# Sensors_CAN.net
KiCad netlist of a schematic drawn in Altium Designer
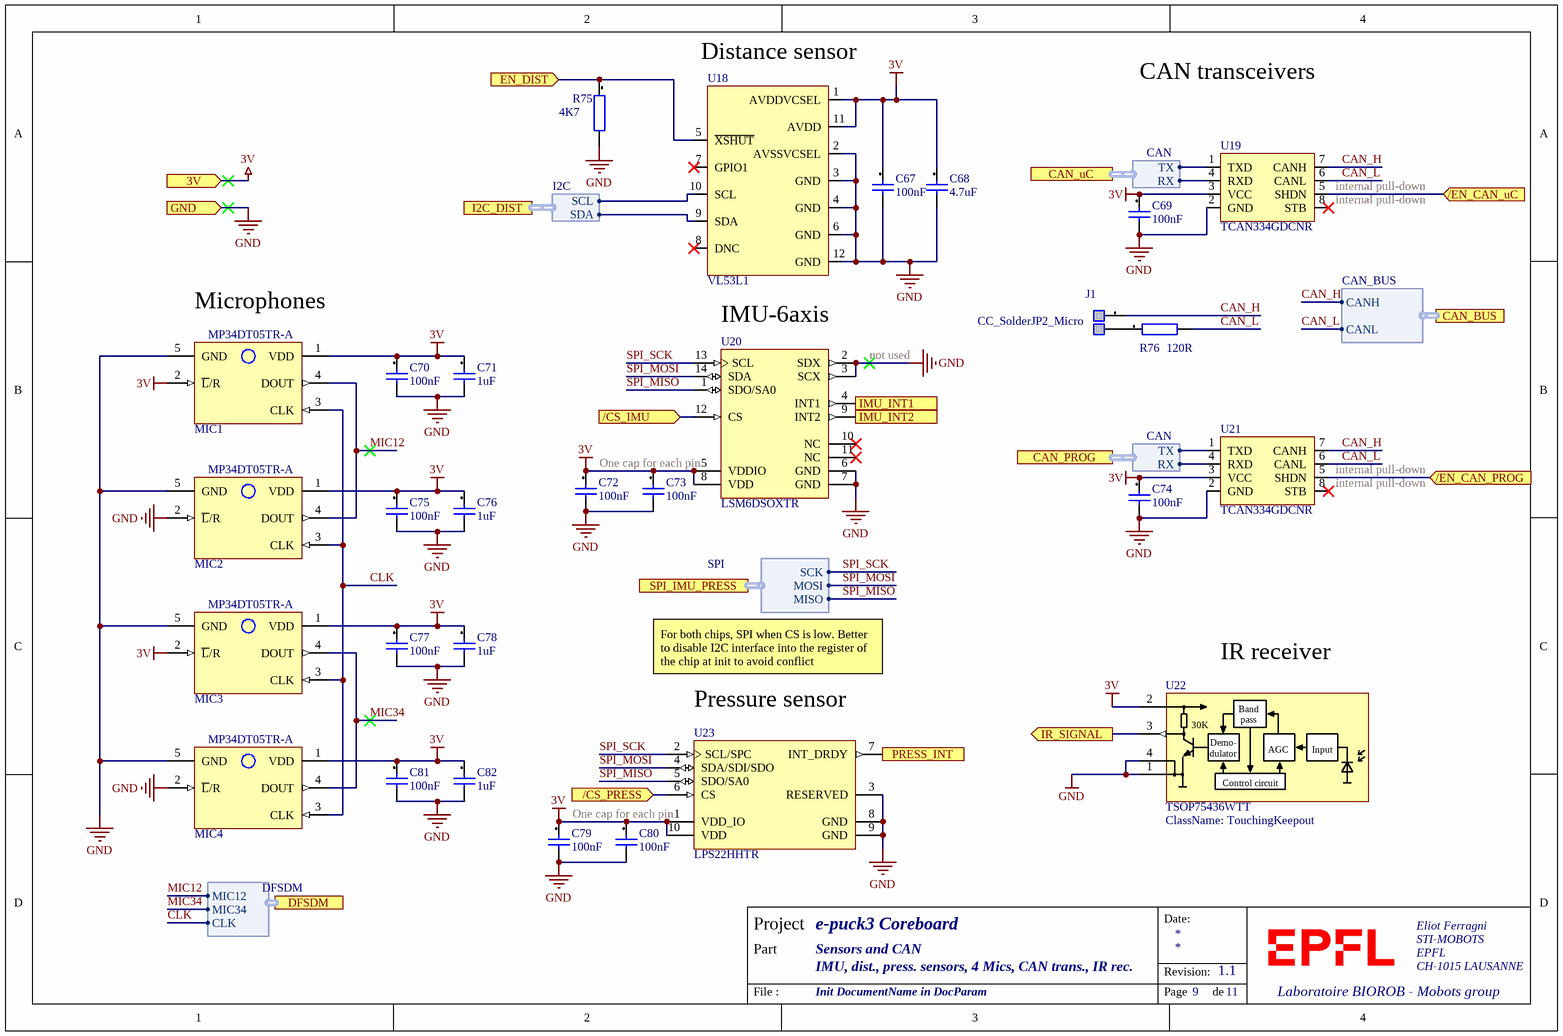
[diagram p0: Sensors + CAN.SchDoc]

(export (version "E")
  (design (tool "Eeschema 10.0.6"))
  (components
    (comp (ref "C67")
      (value "100nF")
      (footprint "CAPC0201(0603)33_L")
      (description "Capacitor 0201")
      (libsource (lib "LSRO1Altium") (part "CAP-NP"))
    )
    (comp (ref "C68")
      (value "4.7uF")
      (footprint "CAPC0201(0603)33_L")
      (description "Capacitor 0201")
      (libsource (lib "LSRO1Altium") (part "CAP-NP"))
    )
    (comp (ref "C69")
      (value "100nF")
      (footprint "CAPC0201(0603)33_L")
      (description "Capacitor 0201")
      (libsource (lib "LSRO1Altium") (part "CAP-NP"))
    )
    (comp (ref "C70")
      (value "100nF")
      (footprint "CAPC0201(0603)33_L")
      (description "Capacitor 0201")
      (libsource (lib "LSRO1Altium") (part "CAP-NP"))
    )
    (comp (ref "C71")
      (value "1uF")
      (footprint "CAPC0201(0603)33_L")
      (description "Capacitor 0201")
      (libsource (lib "LSRO1Altium") (part "CAP-NP"))
    )
    (comp (ref "C72")
      (value "100nF")
      (footprint "CAPC0201(0603)33_L")
      (description "Capacitor 0201")
      (libsource (lib "LSRO1Altium") (part "CAP-NP"))
    )
    (comp (ref "C73")
      (value "100nF")
      (footprint "CAPC0201(0603)33_L")
      (description "Capacitor 0201")
      (libsource (lib "LSRO1Altium") (part "CAP-NP"))
    )
    (comp (ref "C74")
      (value "100nF")
      (footprint "CAPC0201(0603)33_L")
      (description "Capacitor 0201")
      (libsource (lib "LSRO1Altium") (part "CAP-NP"))
    )
    (comp (ref "C75")
      (value "100nF")
      (footprint "CAPC0201(0603)33_L")
      (description "Capacitor 0201")
      (libsource (lib "LSRO1Altium") (part "CAP-NP"))
    )
    (comp (ref "C76")
      (value "1uF")
      (footprint "CAPC0201(0603)33_L")
      (description "Capacitor 0201")
      (libsource (lib "LSRO1Altium") (part "CAP-NP"))
    )
    (comp (ref "C77")
      (value "100nF")
      (footprint "CAPC0201(0603)33_L")
      (description "Capacitor 0201")
      (libsource (lib "LSRO1Altium") (part "CAP-NP"))
    )
    (comp (ref "C78")
      (value "1uF")
      (footprint "CAPC0201(0603)33_L")
      (description "Capacitor 0201")
      (libsource (lib "LSRO1Altium") (part "CAP-NP"))
    )
    (comp (ref "C79")
      (value "100nF")
      (footprint "CAPC0201(0603)33_L")
      (description "Capacitor 0201")
      (libsource (lib "LSRO1Altium") (part "CAP-NP"))
    )
    (comp (ref "C80")
      (value "100nF")
      (footprint "CAPC0201(0603)33_L")
      (description "Capacitor 0201")
      (libsource (lib "LSRO1Altium") (part "CAP-NP"))
    )
    (comp (ref "C81")
      (value "100nF")
      (footprint "CAPC0201(0603)33_L")
      (description "Capacitor 0201")
      (libsource (lib "LSRO1Altium") (part "CAP-NP"))
    )
    (comp (ref "C82")
      (value "1uF")
      (footprint "CAPC0201(0603)33_L")
      (description "Capacitor 0201")
      (libsource (lib "LSRO1Altium") (part "CAP-NP"))
    )
    (comp (ref "J1")
      (value "CC_SolderJP2_Micro")
      (footprint "CC_SolderJP_U")
      (description "Micro Solder Jumper 2 leads")
      (libsource (lib "LSRO1Altium") (part "SolderJP2"))
    )
    (comp (ref "MIC1")
      (value "MP34DT05TR-A")
      (footprint "MIC-PACK_MP34DT05-A(Primary)")
      (description "MEMS AUD MIC SENSOR OMNI 4HCLGA")
      (fields (field (name "MANUFACTURER") "STMicroelectronics"))
      (libsource (lib "Schlib") (part "MP34DT05TR-A"))
    )
    (comp (ref "MIC2")
      (value "MP34DT05TR-A")
      (footprint "MIC-PACK_MP34DT05-A(Primary)")
      (description "MEMS AUD MIC SENSOR OMNI 4HCLGA")
      (fields (field (name "MANUFACTURER") "STMicroelectronics"))
      (libsource (lib "Schlib") (part "MP34DT05TR-A"))
    )
    (comp (ref "MIC3")
      (value "MP34DT05TR-A")
      (footprint "MIC-PACK_MP34DT05-A(Primary)")
      (description "MEMS AUD MIC SENSOR OMNI 4HCLGA")
      (fields (field (name "MANUFACTURER") "STMicroelectronics"))
      (libsource (lib "Schlib") (part "MP34DT05TR-A"))
    )
    (comp (ref "MIC4")
      (value "MP34DT05TR-A")
      (footprint "MIC-PACK_MP34DT05-A(Primary)")
      (description "MEMS AUD MIC SENSOR OMNI 4HCLGA")
      (fields (field (name "MANUFACTURER") "STMicroelectronics"))
      (libsource (lib "Schlib") (part "MP34DT05TR-A"))
    )
    (comp (ref "R75")
      (value "4K7")
      (footprint "RESC0201(0603)_L")
      (description "Resistor 0201")
      (libsource (lib "LSRO1Altium") (part "RES"))
    )
    (comp (ref "R76")
      (value "120R")
      (footprint "RESC0201(0603)_L")
      (description "Resistor 0201")
      (libsource (lib "LSRO1Altium") (part "RES"))
    )
    (comp (ref "U18")
      (value "VL53L1")
      (footprint "VL53L1x")
      (fields
        (field (name "MANUFACTURER") "STMicroelectronics")
        (field (name "MANUFACTURER PART NUMBER") "VL53L1CXV0FY/1")
        (field (name "BASE PART NUMBER") "VL53L1X")
      )
      (libsource (lib "Schlib") (part "VL53L1CXV0FY/1_1"))
    )
    (comp (ref "U19")
      (value "TCAN334GDCNR")
      (footprint "SOT-23-8")
      (description "IC TXRX CAN 3.3V SOT23-8")
      (fields
        (field (name "MANUFACTURER") "Texas Instruments")
        (field (name "MANUFACTURER PART NUMBER") "TCAN334GDCNR")
      )
      (libsource (lib "Schlib") (part "TCAN334GDCNR"))
    )
    (comp (ref "U20")
      (value "LSM6DSOXTR")
      (footprint "STM_LGA_14L")
      (description "IMU 6-AXIS")
      (fields
        (field (name "MANUFACTURER") "STMicroelectronics")
        (field (name "MANUFACTURER PART NUMBER") "LSM6DSOXTR")
      )
      (libsource (lib "Schlib") (part "LSM6DSOXTR"))
    )
    (comp (ref "U21")
      (value "TCAN334GDCNR")
      (footprint "SOT-23-8")
      (description "IC TXRX CAN 3.3V SOT23-8")
      (fields
        (field (name "MANUFACTURER") "Texas Instruments")
        (field (name "MANUFACTURER PART NUMBER") "TCAN334GDCNR")
      )
      (libsource (lib "Schlib") (part "TCAN334GDCNR"))
    )
    (comp (ref "U22")
      (value "TSOP75436WTT")
      (footprint "VISHAY-TSOP752-754")
      (description "Vishay 	TSOP75436WTT IR Receiver Modules for Remote Control Systems")
      (fields (field (name "MANUFACTURER") "Vishay") (field (name "CLASSNAME") "TouchingKeepout"))
      (libsource (lib "Schlib") (part "TSOP752-754"))
    )
    (comp (ref "U23")
      (value "LPS22HHTR")
      (footprint "STM_HLGA_10L")
      (description "Pressure Sensor")
      (fields
        (field (name "MANUFACTURER") "STMicroelectronics")
        (field (name "MANUFACTURER PART NUMBER") "LPS22HHTR")
      )
      (libsource (lib "Schlib") (part "LPS22HHTR"))
    )
  )
  (nets
    (net (code "6") (name "/CAN_H") (class "Default")
      (node (ref "J1") (pin "1") (pintype "passive"))
      (node (ref "U19") (pin "7") (pinfunction "CANH_7") (pintype "passive"))
      (node (ref "U21") (pin "7") (pinfunction "CANH_7") (pintype "passive"))
    )
    (net (code "7") (name "/CAN_L") (class "Default")
      (node (ref "R76") (pin "2") (pinfunction "2_2") (pintype "passive"))
      (node (ref "U19") (pin "6") (pinfunction "CANL_6") (pintype "passive"))
      (node (ref "U21") (pin "6") (pinfunction "CANL_6") (pintype "passive"))
    )
    (net (code "8") (name "/CLK") (class "Default")
      (node (ref "MIC1") (pin "3") (pinfunction "CLK_3") (pintype "input"))
      (node (ref "MIC2") (pin "3") (pinfunction "CLK_3") (pintype "input"))
      (node (ref "MIC3") (pin "3") (pinfunction "CLK_3") (pintype "input"))
      (node (ref "MIC4") (pin "3") (pinfunction "CLK_3") (pintype "input"))
    )
    (net (code "9") (name "/EN_DIST") (class "Default")
      (node (ref "R75") (pin "1") (pinfunction "1_1") (pintype "passive"))
      (node (ref "U18") (pin "5") (pinfunction "~{XSHUT}_5") (pintype "passive"))
    )
    (net (code "10") (name "/IMU_INT1") (class "Default")
      (node (ref "U20") (pin "4") (pinfunction "INT1_4") (pintype "output"))
    )
    (net (code "11") (name "/IMU_INT2") (class "Default")
      (node (ref "U20") (pin "9") (pinfunction "INT2_9") (pintype "output"))
    )
    (net (code "12") (name "/IR_SIGNAL") (class "Default")
      (node (ref "U22") (pin "3") (pinfunction "OUT_3") (pintype "output"))
    )
    (net (code "15") (name "/PRESS_INT") (class "Default")
      (node (ref "U23") (pin "7") (pinfunction "INT_DRDY_7") (pintype "output"))
    )
    (net (code "16") (name "/SCL") (class "Default")
      (node (ref "U18") (pin "10") (pinfunction "SCL_10") (pintype "passive"))
    )
    (net (code "17") (name "/SDA") (class "Default")
      (node (ref "U18") (pin "9") (pinfunction "SDA_9") (pintype "passive"))
    )
    (net (code "18") (name "/SPI_MISO") (class "Default")
      (node (ref "U20") (pin "1") (pinfunction "SDO/SA0_1") (pintype "bidirectional"))
      (node (ref "U23") (pin "5") (pinfunction "SDO/SA0_5") (pintype "bidirectional"))
    )
    (net (code "19") (name "/SPI_MOSI") (class "Default")
      (node (ref "U20") (pin "14") (pinfunction "SDA_14") (pintype "bidirectional"))
      (node (ref "U23") (pin "4") (pinfunction "SDA/SDI/SDO_4") (pintype "bidirectional"))
    )
    (net (code "20") (name "/SPI_SCK") (class "Default")
      (node (ref "U20") (pin "13") (pinfunction "SCL_13") (pintype "input"))
      (node (ref "U23") (pin "2") (pinfunction "SCL/SPC_2") (pintype "input"))
    )
    (net (code "26") (name "/{slash}CS_IMU") (class "Default")
      (node (ref "U20") (pin "12") (pinfunction "CS_12") (pintype "input"))
    )
    (net (code "27") (name "/{slash}CS_PRESS") (class "Default")
      (node (ref "U23") (pin "6") (pinfunction "CS_6") (pintype "input"))
    )
    (net (code "28") (name "/{slash}EN_CAN_PROG") (class "Default")
      (node (ref "U21") (pin "5") (pinfunction "SHDN_5") (pintype "passive"))
    )
    (net (code "29") (name "/{slash}EN_CAN_uC") (class "Default")
      (node (ref "U19") (pin "5") (pinfunction "SHDN_5") (pintype "passive"))
    )
    (net (code "30") (name "3V") (class "Default")
      (node (ref "C67") (pin "1") (pinfunction "1_1") (pintype "passive"))
      (node (ref "C68") (pin "1") (pinfunction "1_1") (pintype "passive"))
      (node (ref "C69") (pin "1") (pinfunction "1_1") (pintype "passive"))
      (node (ref "C70") (pin "1") (pinfunction "1_1") (pintype "passive"))
      (node (ref "C71") (pin "1") (pinfunction "1_1") (pintype "passive"))
      (node (ref "C72") (pin "1") (pinfunction "1_1") (pintype "passive"))
      (node (ref "C73") (pin "1") (pinfunction "1_1") (pintype "passive"))
      (node (ref "C74") (pin "1") (pinfunction "1_1") (pintype "passive"))
      (node (ref "C75") (pin "1") (pinfunction "1_1") (pintype "passive"))
      (node (ref "C76") (pin "1") (pinfunction "1_1") (pintype "passive"))
      (node (ref "C77") (pin "1") (pinfunction "1_1") (pintype "passive"))
      (node (ref "C78") (pin "1") (pinfunction "1_1") (pintype "passive"))
      (node (ref "C79") (pin "1") (pinfunction "1_1") (pintype "passive"))
      (node (ref "C80") (pin "1") (pinfunction "1_1") (pintype "passive"))
      (node (ref "C81") (pin "1") (pinfunction "1_1") (pintype "passive"))
      (node (ref "C82") (pin "1") (pinfunction "1_1") (pintype "passive"))
      (node (ref "MIC1") (pin "1") (pinfunction "VDD_1") (pintype "power_in"))
      (node (ref "MIC1") (pin "2") (pinfunction "~{L}/R_2") (pintype "input"))
      (node (ref "MIC2") (pin "1") (pinfunction "VDD_1") (pintype "power_in"))
      (node (ref "MIC3") (pin "1") (pinfunction "VDD_1") (pintype "power_in"))
      (node (ref "MIC3") (pin "2") (pinfunction "~{L}/R_2") (pintype "input"))
      (node (ref "MIC4") (pin "1") (pinfunction "VDD_1") (pintype "power_in"))
      (node (ref "U18") (pin "1") (pinfunction "AVDDVCSEL_1") (pintype "power_in"))
      (node (ref "U18") (pin "11") (pinfunction "AVDD_11") (pintype "power_in"))
      (node (ref "U19") (pin "3") (pinfunction "VCC_3") (pintype "passive"))
      (node (ref "U20") (pin "5") (pinfunction "VDDIO_5") (pintype "power_in"))
      (node (ref "U20") (pin "8") (pinfunction "VDD_8") (pintype "power_in"))
      (node (ref "U21") (pin "3") (pinfunction "VCC_3") (pintype "passive"))
      (node (ref "U22") (pin "2") (pinfunction "VS_2") (pintype "power_in"))
      (node (ref "U23") (pin "1") (pinfunction "VDD_IO_1") (pintype "power_in"))
      (node (ref "U23") (pin "10") (pinfunction "VDD_10") (pintype "power_in"))
    )
    (net (code "31") (name "GND") (class "Default")
      (node (ref "C67") (pin "2") (pinfunction "2_2") (pintype "passive"))
      (node (ref "C68") (pin "2") (pinfunction "2_2") (pintype "passive"))
      (node (ref "C69") (pin "2") (pinfunction "2_2") (pintype "passive"))
      (node (ref "C70") (pin "2") (pinfunction "2_2") (pintype "passive"))
      (node (ref "C71") (pin "2") (pinfunction "2_2") (pintype "passive"))
      (node (ref "C72") (pin "2") (pinfunction "2_2") (pintype "passive"))
      (node (ref "C73") (pin "2") (pinfunction "2_2") (pintype "passive"))
      (node (ref "C74") (pin "2") (pinfunction "2_2") (pintype "passive"))
      (node (ref "C75") (pin "2") (pinfunction "2_2") (pintype "passive"))
      (node (ref "C76") (pin "2") (pinfunction "2_2") (pintype "passive"))
      (node (ref "C77") (pin "2") (pinfunction "2_2") (pintype "passive"))
      (node (ref "C78") (pin "2") (pinfunction "2_2") (pintype "passive"))
      (node (ref "C79") (pin "2") (pinfunction "2_2") (pintype "passive"))
      (node (ref "C80") (pin "2") (pinfunction "2_2") (pintype "passive"))
      (node (ref "C81") (pin "2") (pinfunction "2_2") (pintype "passive"))
      (node (ref "C82") (pin "2") (pinfunction "2_2") (pintype "passive"))
      (node (ref "MIC1") (pin "5") (pinfunction "GND_5") (pintype "power_in"))
      (node (ref "MIC2") (pin "2") (pinfunction "~{L}/R_2") (pintype "input"))
      (node (ref "MIC2") (pin "5") (pinfunction "GND_5") (pintype "power_in"))
      (node (ref "MIC3") (pin "5") (pinfunction "GND_5") (pintype "power_in"))
      (node (ref "MIC4") (pin "2") (pinfunction "~{L}/R_2") (pintype "input"))
      (node (ref "MIC4") (pin "5") (pinfunction "GND_5") (pintype "power_in"))
      (node (ref "R75") (pin "2") (pinfunction "2_2") (pintype "passive"))
      (node (ref "U18") (pin "12") (pinfunction "GND_12") (pintype "power_in"))
      (node (ref "U18") (pin "2") (pinfunction "AVSSVCSEL_2") (pintype "power_in"))
      (node (ref "U18") (pin "3") (pinfunction "GND_3") (pintype "power_in"))
      (node (ref "U18") (pin "4") (pinfunction "GND_4") (pintype "power_in"))
      (node (ref "U18") (pin "6") (pinfunction "GND_6") (pintype "power_in"))
      (node (ref "U19") (pin "2") (pinfunction "GND_2") (pintype "passive"))
      (node (ref "U20") (pin "2") (pinfunction "SDX_2") (pintype "output"))
      (node (ref "U20") (pin "3") (pinfunction "SCX_3") (pintype "output"))
      (node (ref "U20") (pin "6") (pinfunction "GND_6") (pintype "power_in"))
      (node (ref "U20") (pin "7") (pinfunction "GND_7") (pintype "power_in"))
      (node (ref "U21") (pin "2") (pinfunction "GND_2") (pintype "passive"))
      (node (ref "U22") (pin "1") (pinfunction "GND_1") (pintype "power_in"))
      (node (ref "U22") (pin "4") (pinfunction "GND_4") (pintype "power_in"))
      (node (ref "U23") (pin "3") (pinfunction "RESERVED_3") (pintype "power_in"))
      (node (ref "U23") (pin "8") (pinfunction "GND_8") (pintype "power_in"))
      (node (ref "U23") (pin "9") (pinfunction "GND_9") (pintype "power_in"))
    )
    (net (code "32") (name "Net-(J1-Pad2)") (class "Default")
      (node (ref "J1") (pin "2") (pintype "passive"))
      (node (ref "R76") (pin "1") (pinfunction "1_1") (pintype "passive"))
    )
    (net (code "33") (name "Net-(MIC1-DOUT)") (class "Default")
      (node (ref "MIC1") (pin "4") (pinfunction "DOUT_4") (pintype "output"))
      (node (ref "MIC2") (pin "4") (pinfunction "DOUT_4") (pintype "output"))
    )
    (net (code "34") (name "Net-(MIC3-DOUT)") (class "Default")
      (node (ref "MIC3") (pin "4") (pinfunction "DOUT_4") (pintype "output"))
      (node (ref "MIC4") (pin "4") (pinfunction "DOUT_4") (pintype "output"))
    )
    (net (code "35") (name "unconnected-(U18-DNC-Pad8)") (class "Default")
      (node (ref "U18") (pin "8") (pinfunction "DNC_8") (pintype "passive+no_connect"))
    )
    (net (code "36") (name "unconnected-(U18-GPIO1-Pad7)") (class "Default")
      (node (ref "U18") (pin "7") (pinfunction "GPIO1_7") (pintype "passive+no_connect"))
    )
    (net (code "37") (name "unconnected-(U19-RXD-Pad4)") (class "Default")
      (node (ref "U19") (pin "4") (pinfunction "RXD_4") (pintype "passive"))
    )
    (net (code "38") (name "unconnected-(U19-STB-Pad8)") (class "Default")
      (node (ref "U19") (pin "8") (pinfunction "STB_8") (pintype "passive+no_connect"))
    )
    (net (code "39") (name "unconnected-(U19-TXD-Pad1)") (class "Default")
      (node (ref "U19") (pin "1") (pinfunction "TXD_1") (pintype "passive"))
    )
    (net (code "40") (name "unconnected-(U20-NC-Pad10)") (class "Default")
      (node (ref "U20") (pin "10") (pinfunction "NC_10") (pintype "passive+no_connect"))
    )
    (net (code "41") (name "unconnected-(U20-NC-Pad11)") (class "Default")
      (node (ref "U20") (pin "11") (pinfunction "NC_11") (pintype "passive+no_connect"))
    )
    (net (code "42") (name "unconnected-(U21-RXD-Pad4)") (class "Default")
      (node (ref "U21") (pin "4") (pinfunction "RXD_4") (pintype "passive"))
    )
    (net (code "43") (name "unconnected-(U21-STB-Pad8)") (class "Default")
      (node (ref "U21") (pin "8") (pinfunction "STB_8") (pintype "passive+no_connect"))
    )
    (net (code "44") (name "unconnected-(U21-TXD-Pad1)") (class "Default")
      (node (ref "U21") (pin "1") (pinfunction "TXD_1") (pintype "passive"))
    )
  )
)
